# rs485.net
KiCad netlist of a schematic drawn in Altium Designer
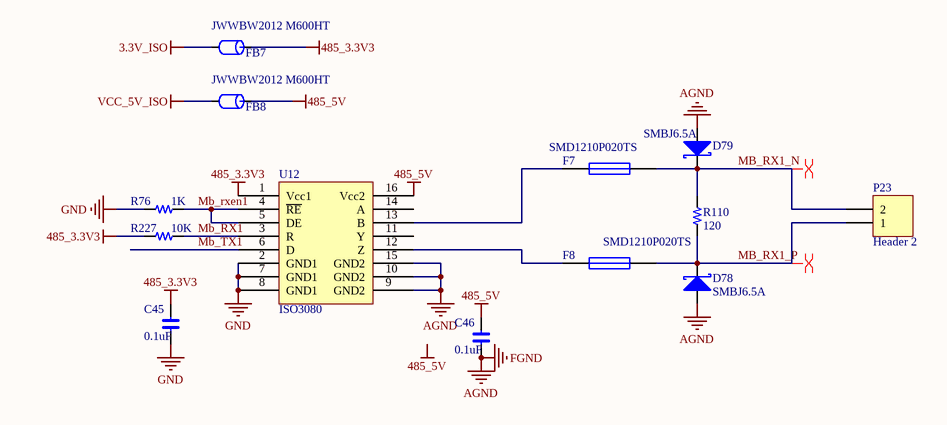
[diagram p0: rs485.SchDoc]

(export (version "E")
  (design (tool "Eeschema 10.0.6"))
  (components
    (comp (ref "C45")
      (value "0.1uF")
      (footprint "0603C")
      (description "C")
      (libsource (lib "Schlib_20110825") (part "C"))
    )
    (comp (ref "C46")
      (value "0.1uF")
      (footprint "0603C")
      (description "C")
      (libsource (lib "Schlib_20110825") (part "C"))
    )
    (comp (ref "D78")
      (value "SMBJ6.5A")
      (footprint "SMB")
      (description "Schottky Diode")
      (libsource (lib "*") (part "DIODE S"))
    )
    (comp (ref "D79")
      (value "SMBJ6.5A")
      (footprint "SMB")
      (description "Schottky Diode")
      (libsource (lib "*") (part "DIODE S"))
    )
    (comp (ref "F7")
      (value "SMD1210P020TS")
      (footprint "1206R")
      (description "Fuse")
      (fields (field (name "PUBLISHER") "Altium Limited"))
      (libsource (lib "Miscellaneous Devices") (part "Fuse 1"))
    )
    (comp (ref "F8")
      (value "SMD1210P020TS")
      (footprint "1206R")
      (description "Fuse")
      (fields (field (name "PUBLISHER") "Altium Limited"))
      (libsource (lib "Miscellaneous Devices") (part "Fuse 1"))
    )
    (comp (ref "FB7")
      (value "JWWBW2012 M600HT")
      (footprint "0805CZ")
      (libsource (lib "Schlib_20110825") (part "FB"))
    )
    (comp (ref "FB8")
      (value "JWWBW2012 M600HT")
      (footprint "0805CZ")
      (libsource (lib "Schlib_20110825") (part "FB"))
    )
    (comp (ref "P23")
      (value "Header 2")
      (footprint "2X2.54MMZ")
      (description "Header, 2-Pin")
      (fields (field (name "PUBLISHER") "Altium Limited"))
      (libsource (lib "Miscellaneous Connectors") (part "Header 2"))
    )
    (comp (ref "R76") (value "1K") (footprint "0603R") (description "R") (libsource (lib "JRJ_1") (part "R")))
    (comp (ref "R110")
      (value "120")
      (footprint "0603R")
      (description "R")
      (libsource (lib "JRJ_1") (part "R"))
    )
    (comp (ref "R227")
      (value "10K")
      (footprint "0603R")
      (description "R")
      (libsource (lib "JRJ_1") (part "R"))
    )
    (comp (ref "U12") (value "ISO3080") (footprint "SO-16") (libsource (lib "Schlib1") (part "ISO3080")))
  )
  (nets
    (net (code "1") (name "/MB_RX1_N") (class "Default")
      (node (ref "D79") (pin "2") (pinfunction "K_2") (pintype "passive"))
      (node (ref "F7") (pin "2") (pinfunction "2_2") (pintype "passive"))
      (node (ref "P23") (pin "2") (pinfunction "2_2") (pintype "passive"))
      (node (ref "R110") (pin "1") (pintype "passive"))
    )
    (net (code "2") (name "/MB_RX1_P") (class "Default")
      (node (ref "D78") (pin "2") (pinfunction "K_2") (pintype "passive"))
      (node (ref "F8") (pin "2") (pinfunction "2_2") (pintype "passive"))
      (node (ref "P23") (pin "1") (pinfunction "1_1") (pintype "passive"))
      (node (ref "R110") (pin "2") (pintype "passive"))
    )
    (net (code "3") (name "/Mb_RX1") (class "Default")
      (node (ref "R227") (pin "1") (pintype "passive"))
      (node (ref "U12") (pin "3") (pinfunction "R_3") (pintype "passive"))
    )
    (net (code "4") (name "/Mb_TX1") (class "Default")
      (node (ref "U12") (pin "6") (pinfunction "D_6") (pintype "passive"))
    )
    (net (code "5") (name "/Mb_rxen1") (class "Default")
      (node (ref "R76") (pin "1") (pintype "passive"))
      (node (ref "U12") (pin "4") (pinfunction "~{RE}_4") (pintype "passive"))
      (node (ref "U12") (pin "5") (pinfunction "DE_5") (pintype "passive"))
    )
    (net (code "6") (name "3.3V_ISO") (class "Default") (node (ref "FB7") (pin "2") (pintype "passive")))
    (net (code "7") (name "485_3.3V3") (class "Default")
      (node (ref "C45") (pin "2") (pintype "passive"))
      (node (ref "FB7") (pin "1") (pintype "passive"))
      (node (ref "R227") (pin "2") (pintype "passive"))
      (node (ref "U12") (pin "1") (pinfunction "Vcc1_1") (pintype "passive"))
    )
    (net (code "8") (name "485_5V") (class "Default")
      (node (ref "C46") (pin "2") (pintype "passive"))
      (node (ref "FB8") (pin "1") (pintype "passive"))
      (node (ref "U12") (pin "16") (pinfunction "Vcc2_16") (pintype "passive"))
    )
    (net (code "9") (name "AGND") (class "Default")
      (node (ref "C46") (pin "1") (pintype "passive"))
      (node (ref "D78") (pin "1") (pinfunction "A_1") (pintype "passive"))
      (node (ref "D79") (pin "1") (pinfunction "A_1") (pintype "passive"))
      (node (ref "U12") (pin "10") (pinfunction "GND2_10") (pintype "passive"))
      (node (ref "U12") (pin "15") (pinfunction "GND2_15") (pintype "passive"))
      (node (ref "U12") (pin "9") (pinfunction "GND2_9") (pintype "passive"))
    )
    (net (code "10") (name "GND") (class "Default")
      (node (ref "C45") (pin "1") (pintype "passive"))
      (node (ref "R76") (pin "2") (pintype "passive"))
      (node (ref "U12") (pin "2") (pinfunction "GND1_2") (pintype "passive"))
      (node (ref "U12") (pin "7") (pinfunction "GND1_7") (pintype "passive"))
      (node (ref "U12") (pin "8") (pinfunction "GND1_8") (pintype "passive"))
    )
    (net (code "11") (name "Net-(U12-B)") (class "Default")
      (node (ref "F7") (pin "1") (pinfunction "1_1") (pintype "passive"))
      (node (ref "U12") (pin "13") (pinfunction "B_13") (pintype "passive"))
    )
    (net (code "12") (name "Net-(U12-Z)") (class "Default")
      (node (ref "F8") (pin "1") (pinfunction "1_1") (pintype "passive"))
      (node (ref "U12") (pin "12") (pinfunction "Z_12") (pintype "passive"))
    )
    (net (code "13") (name "VCC_5V_ISO") (class "Default") (node (ref "FB8") (pin "2") (pintype "passive")))
    (net (code "14") (name "unconnected-(U12-A-Pad14)") (class "Default")
      (node (ref "U12") (pin "14") (pinfunction "A_14") (pintype "passive"))
    )
    (net (code "15") (name "unconnected-(U12-Y-Pad11)") (class "Default")
      (node (ref "U12") (pin "11") (pinfunction "Y_11") (pintype "passive"))
    )
  )
)
